# BH67172NUX.net
KiCad netlist of a schematic drawn in EAGLE
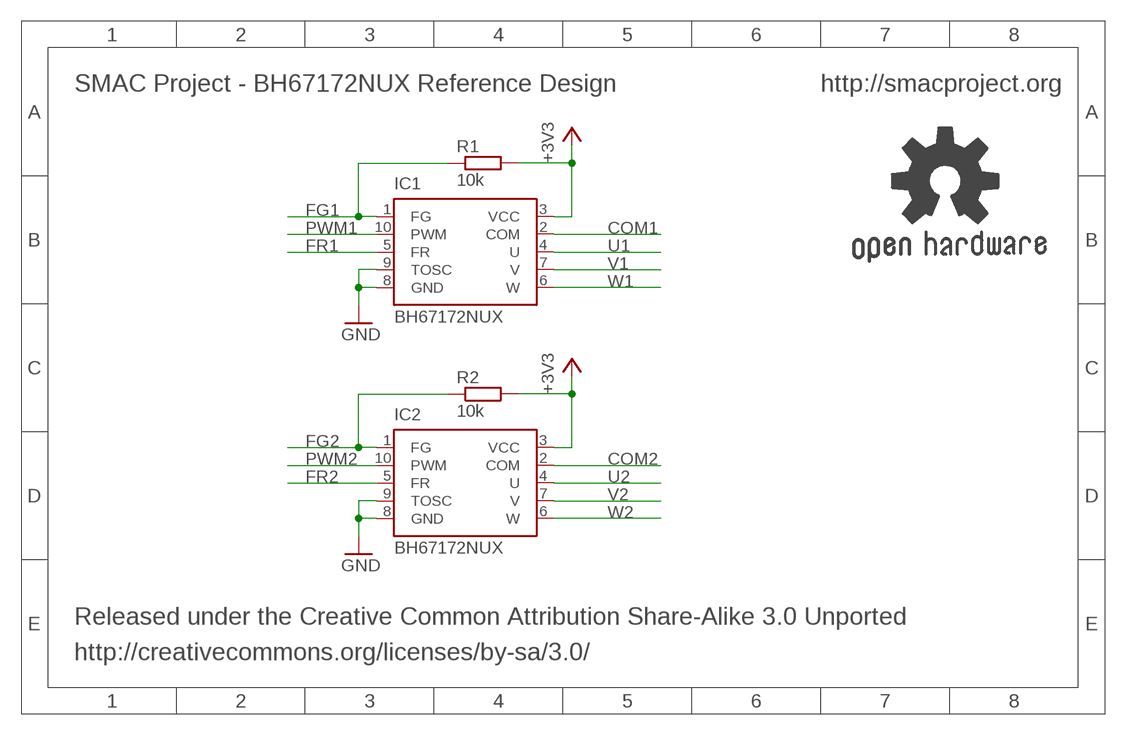
[diagram p0: schematic, sheet 1]

(export (version "E")
  (design (tool "Eeschema 10.0.6"))
  (components
    (comp (ref "GOLD_ORB_SM1")
      (value "OSHWLOGO_REF_SM")
      (footprint "eagle-import:OSHW2REF")
      (libsource (lib "eagle-import") (part "OSHWLOGO_REF_SM"))
    )
    (comp (ref "IC1")
      (value "BH67172NUX")
      (footprint "eagle-import:VSON010X3030")
      (libsource (lib "eagle-import") (part "BH67172NUX"))
    )
    (comp (ref "IC2")
      (value "BH67172NUX")
      (footprint "eagle-import:VSON010X3030")
      (libsource (lib "eagle-import") (part "BH67172NUX"))
    )
    (comp (ref "R1")
      (value "10k")
      (footprint "eagle-import:R0402")
      (libsource (lib "eagle-import") (part "R-EU_R0402"))
    )
    (comp (ref "R2")
      (value "10k")
      (footprint "eagle-import:R0402")
      (libsource (lib "eagle-import") (part "R-EU_R0402"))
    )
  )
  (nets
    (net (code "1") (name "+3V3") (class "Default")
      (node (ref "IC1") (pin "3") (pinfunction "VCC_3") (pintype "power_in"))
      (node (ref "IC2") (pin "3") (pinfunction "VCC_3") (pintype "power_in"))
      (node (ref "R1") (pin "2") (pinfunction "2_2") (pintype "passive"))
      (node (ref "R2") (pin "2") (pinfunction "2_2") (pintype "passive"))
    )
    (net (code "2") (name "/COM1") (class "Default")
      (node (ref "IC1") (pin "2") (pinfunction "COM_2") (pintype "output"))
    )
    (net (code "3") (name "/COM2") (class "Default")
      (node (ref "IC2") (pin "2") (pinfunction "COM_2") (pintype "output"))
    )
    (net (code "4") (name "/FG1") (class "Default")
      (node (ref "IC1") (pin "1") (pinfunction "FG_1") (pintype "output"))
      (node (ref "R1") (pin "1") (pinfunction "1_1") (pintype "passive"))
    )
    (net (code "5") (name "/FG2") (class "Default")
      (node (ref "IC2") (pin "1") (pinfunction "FG_1") (pintype "output"))
      (node (ref "R2") (pin "1") (pinfunction "1_1") (pintype "passive"))
    )
    (net (code "6") (name "/FR1") (class "Default")
      (node (ref "IC1") (pin "5") (pinfunction "FR_5") (pintype "input"))
    )
    (net (code "7") (name "/FR2") (class "Default")
      (node (ref "IC2") (pin "5") (pinfunction "FR_5") (pintype "input"))
    )
    (net (code "8") (name "/PWM1") (class "Default")
      (node (ref "IC1") (pin "10") (pinfunction "PWM_10") (pintype "input"))
    )
    (net (code "9") (name "/PWM2") (class "Default")
      (node (ref "IC2") (pin "10") (pinfunction "PWM_10") (pintype "input"))
    )
    (net (code "10") (name "/U1") (class "Default")
      (node (ref "IC1") (pin "4") (pinfunction "U_4") (pintype "output"))
    )
    (net (code "11") (name "/U2") (class "Default")
      (node (ref "IC2") (pin "4") (pinfunction "U_4") (pintype "output"))
    )
    (net (code "12") (name "/V1") (class "Default")
      (node (ref "IC1") (pin "7") (pinfunction "V_7") (pintype "output"))
    )
    (net (code "13") (name "/V2") (class "Default")
      (node (ref "IC2") (pin "7") (pinfunction "V_7") (pintype "output"))
    )
    (net (code "14") (name "/W1") (class "Default")
      (node (ref "IC1") (pin "6") (pinfunction "W_6") (pintype "output"))
    )
    (net (code "15") (name "/W2") (class "Default")
      (node (ref "IC2") (pin "6") (pinfunction "W_6") (pintype "output"))
    )
    (net (code "16") (name "GND") (class "Default")
      (node (ref "IC1") (pin "8") (pinfunction "GND_8") (pintype "power_in"))
      (node (ref "IC1") (pin "9") (pinfunction "TOSC_9") (pintype "passive"))
      (node (ref "IC2") (pin "8") (pinfunction "GND_8") (pintype "power_in"))
      (node (ref "IC2") (pin "9") (pinfunction "TOSC_9") (pintype "passive"))
    )
  )
)
